# Mechanical.net
KiCad netlist of a schematic drawn in Altium Designer
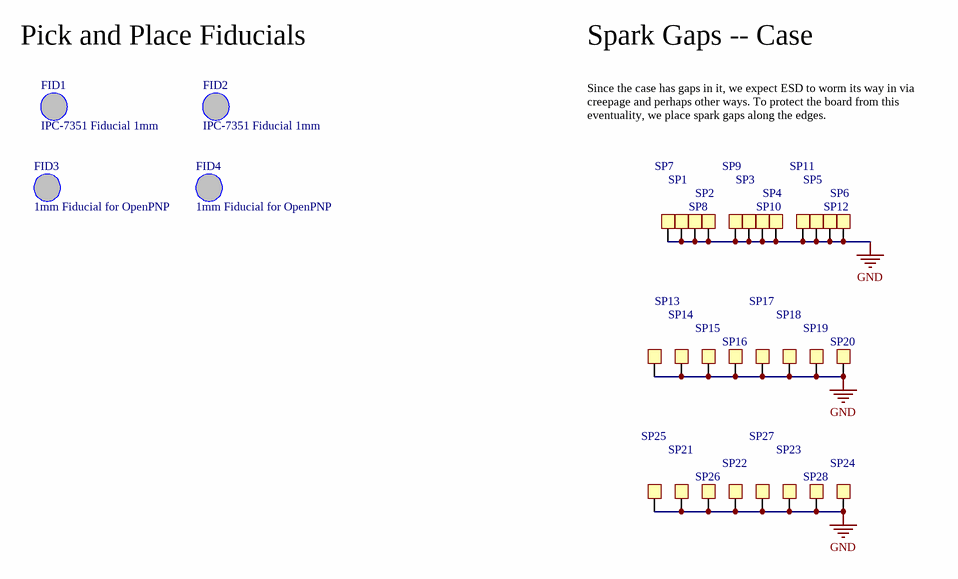
[diagram p0: Mechanical.SchDoc]

(export (version "E")
  (design (tool "Eeschema 10.0.6"))
  (components
    (comp (ref "FID1")
      (value "IPC-7351 Fiducial 1mm")
      (footprint "FIDUCIAL_1.5")
      (libsource (lib "Mechanical") (part "FIDUCIAL_1.5"))
    )
    (comp (ref "FID2")
      (value "IPC-7351 Fiducial 1mm")
      (footprint "FIDUCIAL_1.5")
      (libsource (lib "Mechanical") (part "FIDUCIAL_1.5"))
    )
    (comp (ref "FID3")
      (value "1mm Fiducial for OpenPNP")
      (footprint "FIDUCIAL-NEW")
      (libsource (lib "Mechanical") (part "FIDUCIAL_NEW"))
    )
    (comp (ref "FID4")
      (value "1mm Fiducial for OpenPNP")
      (footprint "FIDUCIAL-NEW")
      (libsource (lib "Mechanical") (part "FIDUCIAL_NEW"))
    )
    (comp (ref "SP1")
      (value "Spark Gap")
      (footprint "SparkGap")
      (description "Open square pad for spark gapping")
      (libsource (lib "PCBFeatures") (part "Spark Gap"))
    )
    (comp (ref "SP2")
      (value "Spark Gap")
      (footprint "SparkGap")
      (description "Open square pad for spark gapping")
      (libsource (lib "PCBFeatures") (part "Spark Gap"))
    )
    (comp (ref "SP3")
      (value "Spark Gap")
      (footprint "SparkGap")
      (description "Open square pad for spark gapping")
      (libsource (lib "PCBFeatures") (part "Spark Gap"))
    )
    (comp (ref "SP4")
      (value "Spark Gap")
      (footprint "SparkGap")
      (description "Open square pad for spark gapping")
      (libsource (lib "PCBFeatures") (part "Spark Gap"))
    )
    (comp (ref "SP5")
      (value "Spark Gap")
      (footprint "SparkGap")
      (description "Open square pad for spark gapping")
      (libsource (lib "PCBFeatures") (part "Spark Gap"))
    )
    (comp (ref "SP6")
      (value "Spark Gap")
      (footprint "SparkGap")
      (description "Open square pad for spark gapping")
      (libsource (lib "PCBFeatures") (part "Spark Gap"))
    )
    (comp (ref "SP7")
      (value "Spark Gap")
      (footprint "SparkGap")
      (description "Open square pad for spark gapping")
      (libsource (lib "PCBFeatures") (part "Spark Gap"))
    )
    (comp (ref "SP8")
      (value "Spark Gap")
      (footprint "SparkGap")
      (description "Open square pad for spark gapping")
      (libsource (lib "PCBFeatures") (part "Spark Gap"))
    )
    (comp (ref "SP9")
      (value "Spark Gap")
      (footprint "SparkGap")
      (description "Open square pad for spark gapping")
      (libsource (lib "PCBFeatures") (part "Spark Gap"))
    )
    (comp (ref "SP10")
      (value "Spark Gap")
      (footprint "SparkGap")
      (description "Open square pad for spark gapping")
      (libsource (lib "PCBFeatures") (part "Spark Gap"))
    )
    (comp (ref "SP11")
      (value "Spark Gap")
      (footprint "SparkGap")
      (description "Open square pad for spark gapping")
      (libsource (lib "PCBFeatures") (part "Spark Gap"))
    )
    (comp (ref "SP12")
      (value "Spark Gap")
      (footprint "SparkGap")
      (description "Open square pad for spark gapping")
      (libsource (lib "PCBFeatures") (part "Spark Gap"))
    )
    (comp (ref "SP13")
      (value "Spark Gap")
      (footprint "SparkGap")
      (description "Open square pad for spark gapping")
      (libsource (lib "PCBFeatures") (part "Spark Gap"))
    )
    (comp (ref "SP14")
      (value "Spark Gap")
      (footprint "SparkGap")
      (description "Open square pad for spark gapping")
      (libsource (lib "PCBFeatures") (part "Spark Gap"))
    )
    (comp (ref "SP15")
      (value "Spark Gap")
      (footprint "SparkGap")
      (description "Open square pad for spark gapping")
      (libsource (lib "PCBFeatures") (part "Spark Gap"))
    )
    (comp (ref "SP16")
      (value "Spark Gap")
      (footprint "SparkGap")
      (description "Open square pad for spark gapping")
      (libsource (lib "PCBFeatures") (part "Spark Gap"))
    )
    (comp (ref "SP17")
      (value "Spark Gap")
      (footprint "SparkGap")
      (description "Open square pad for spark gapping")
      (libsource (lib "PCBFeatures") (part "Spark Gap"))
    )
    (comp (ref "SP18")
      (value "Spark Gap")
      (footprint "SparkGap")
      (description "Open square pad for spark gapping")
      (libsource (lib "PCBFeatures") (part "Spark Gap"))
    )
    (comp (ref "SP19")
      (value "Spark Gap")
      (footprint "SparkGap")
      (description "Open square pad for spark gapping")
      (libsource (lib "PCBFeatures") (part "Spark Gap"))
    )
    (comp (ref "SP20")
      (value "Spark Gap")
      (footprint "SparkGap")
      (description "Open square pad for spark gapping")
      (libsource (lib "PCBFeatures") (part "Spark Gap"))
    )
    (comp (ref "SP21")
      (value "Spark Gap")
      (footprint "SparkGap")
      (description "Open square pad for spark gapping")
      (libsource (lib "PCBFeatures") (part "Spark Gap"))
    )
    (comp (ref "SP22")
      (value "Spark Gap")
      (footprint "SparkGap")
      (description "Open square pad for spark gapping")
      (libsource (lib "PCBFeatures") (part "Spark Gap"))
    )
    (comp (ref "SP23")
      (value "Spark Gap")
      (footprint "SparkGap")
      (description "Open square pad for spark gapping")
      (libsource (lib "PCBFeatures") (part "Spark Gap"))
    )
    (comp (ref "SP24")
      (value "Spark Gap")
      (footprint "SparkGap")
      (description "Open square pad for spark gapping")
      (libsource (lib "PCBFeatures") (part "Spark Gap"))
    )
    (comp (ref "SP25")
      (value "Spark Gap")
      (footprint "SparkGap")
      (description "Open square pad for spark gapping")
      (libsource (lib "PCBFeatures") (part "Spark Gap"))
    )
    (comp (ref "SP26")
      (value "Spark Gap")
      (footprint "SparkGap")
      (description "Open square pad for spark gapping")
      (libsource (lib "PCBFeatures") (part "Spark Gap"))
    )
    (comp (ref "SP27")
      (value "Spark Gap")
      (footprint "SparkGap")
      (description "Open square pad for spark gapping")
      (libsource (lib "PCBFeatures") (part "Spark Gap"))
    )
    (comp (ref "SP28")
      (value "Spark Gap")
      (footprint "SparkGap")
      (description "Open square pad for spark gapping")
      (libsource (lib "PCBFeatures") (part "Spark Gap"))
    )
  )
  (nets
    (net (code "1") (name "GND") (class "Default")
      (node (ref "SP1") (pin "1") (pinfunction "1_1") (pintype "passive"))
      (node (ref "SP10") (pin "1") (pinfunction "1_1") (pintype "passive"))
      (node (ref "SP11") (pin "1") (pinfunction "1_1") (pintype "passive"))
      (node (ref "SP12") (pin "1") (pinfunction "1_1") (pintype "passive"))
      (node (ref "SP13") (pin "1") (pinfunction "1_1") (pintype "passive"))
      (node (ref "SP14") (pin "1") (pinfunction "1_1") (pintype "passive"))
      (node (ref "SP15") (pin "1") (pinfunction "1_1") (pintype "passive"))
      (node (ref "SP16") (pin "1") (pinfunction "1_1") (pintype "passive"))
      (node (ref "SP17") (pin "1") (pinfunction "1_1") (pintype "passive"))
      (node (ref "SP18") (pin "1") (pinfunction "1_1") (pintype "passive"))
      (node (ref "SP19") (pin "1") (pinfunction "1_1") (pintype "passive"))
      (node (ref "SP2") (pin "1") (pinfunction "1_1") (pintype "passive"))
      (node (ref "SP20") (pin "1") (pinfunction "1_1") (pintype "passive"))
      (node (ref "SP21") (pin "1") (pinfunction "1_1") (pintype "passive"))
      (node (ref "SP22") (pin "1") (pinfunction "1_1") (pintype "passive"))
      (node (ref "SP23") (pin "1") (pinfunction "1_1") (pintype "passive"))
      (node (ref "SP24") (pin "1") (pinfunction "1_1") (pintype "passive"))
      (node (ref "SP25") (pin "1") (pinfunction "1_1") (pintype "passive"))
      (node (ref "SP26") (pin "1") (pinfunction "1_1") (pintype "passive"))
      (node (ref "SP27") (pin "1") (pinfunction "1_1") (pintype "passive"))
      (node (ref "SP28") (pin "1") (pinfunction "1_1") (pintype "passive"))
      (node (ref "SP3") (pin "1") (pinfunction "1_1") (pintype "passive"))
      (node (ref "SP4") (pin "1") (pinfunction "1_1") (pintype "passive"))
      (node (ref "SP5") (pin "1") (pinfunction "1_1") (pintype "passive"))
      (node (ref "SP6") (pin "1") (pinfunction "1_1") (pintype "passive"))
      (node (ref "SP7") (pin "1") (pinfunction "1_1") (pintype "passive"))
      (node (ref "SP8") (pin "1") (pinfunction "1_1") (pintype "passive"))
      (node (ref "SP9") (pin "1") (pinfunction "1_1") (pintype "passive"))
    )
    (net (code "2") (name "unconnected-(FID1-Pad1)") (class "Default")
      (node (ref "FID1") (pin "1") (pinfunction "1_1") (pintype "passive"))
    )
    (net (code "3") (name "unconnected-(FID2-Pad1)") (class "Default")
      (node (ref "FID2") (pin "1") (pinfunction "1_1") (pintype "passive"))
    )
    (net (code "4") (name "unconnected-(FID3-Pad1)") (class "Default")
      (node (ref "FID3") (pin "1") (pinfunction "1_1") (pintype "passive"))
    )
    (net (code "5") (name "unconnected-(FID4-Pad1)") (class "Default")
      (node (ref "FID4") (pin "1") (pinfunction "1_1") (pintype "passive"))
    )
  )
)
